# Clock.net
KiCad netlist of a schematic drawn in Altium Designer
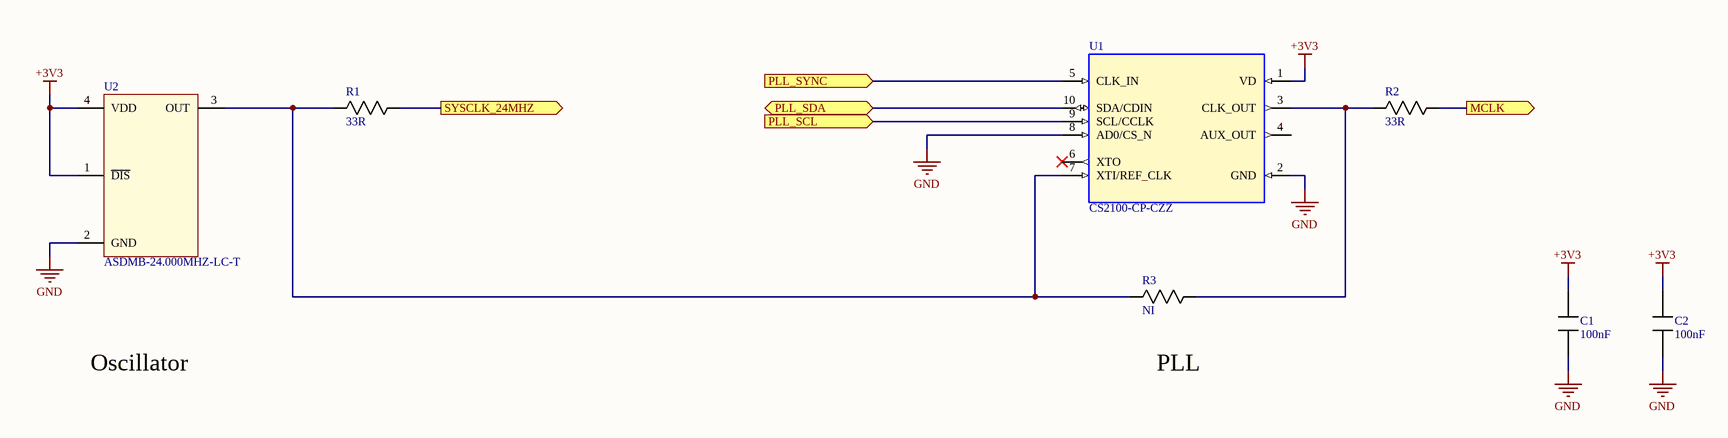
[diagram p0: Clock.SchDoc]

(export (version "E")
  (design (tool "Eeschema 10.0.6"))
  (components
    (comp (ref "C1")
      (value "100nF")
      (footprint "0603")
      (description "Capacitor")
      (fields (field (name "MFG") "Samsung"))
      (libsource (lib "ADAPTONE_CARTE_DE_SON") (part "Capacitor"))
    )
    (comp (ref "C2")
      (value "100nF")
      (footprint "0603")
      (description "Capacitor")
      (fields (field (name "MFG") "Samsung"))
      (libsource (lib "ADAPTONE_CARTE_DE_SON") (part "Capacitor"))
    )
    (comp (ref "R1")
      (value "33R")
      (footprint "0603")
      (description "Resistor")
      (fields (field (name "MFG") "Yageo"))
      (libsource (lib "ADAPTONE_CARTE_DE_SON") (part "Resistor"))
    )
    (comp (ref "R2")
      (value "33R")
      (footprint "0603")
      (description "Resistor")
      (fields (field (name "MFG") "Yageo"))
      (libsource (lib "ADAPTONE_CARTE_DE_SON") (part "Resistor"))
    )
    (comp (ref "R3")
      (value "Resistor")
      (footprint "0603")
      (fields (field (name "NI") "NI"))
      (libsource (lib "ADAPTONE_CARTE_DE_SON") (part "Resistor"))
    )
    (comp (ref "U1")
      (value "CS2100_CP")
      (footprint "MSOP10")
      (description "Fractional-N Clock Multiplier, Crystal Reference, MSOP10")
      (fields (field (name "MFG") "Cirrus Logic") (field (name "MFG_PN") "CS2100-CP-CZZ"))
      (libsource (lib "ADAPTONE_CARTE_DE_SON") (part "CS2100_CP"))
    )
    (comp (ref "U2")
      (value "OSC_ASDMB")
      (footprint "OSC_ADSMB")
      (description "Oscillator; 1V8 to 3V3")
      (fields (field (name "MFG") "Abracon") (field (name "MFG_PN") "ASDMB-24.000MHZ-LC-T"))
      (libsource (lib "ADAPTONE_CARTE_DE_SON") (part "OSC_ASDMB"))
    )
  )
  (nets
    (net (code "1") (name "+3V3") (class "Default")
      (node (ref "C1") (pin "1") (pintype "passive"))
      (node (ref "C2") (pin "1") (pintype "passive"))
      (node (ref "U1") (pin "1") (pinfunction "VD_1") (pintype "input"))
      (node (ref "U2") (pin "1") (pinfunction "~{DIS}_1") (pintype "passive"))
      (node (ref "U2") (pin "4") (pinfunction "VDD_4") (pintype "passive"))
    )
    (net (code "2") (name "/MCLK") (class "Default") (node (ref "R2") (pin "2") (pintype "passive")))
    (net (code "3") (name "/PLL_SCL") (class "Default")
      (node (ref "U1") (pin "9") (pinfunction "SCL/CCLK_9") (pintype "input"))
    )
    (net (code "4") (name "/PLL_SDA") (class "Default")
      (node (ref "U1") (pin "10") (pinfunction "SDA/CDIN_10") (pintype "bidirectional"))
    )
    (net (code "5") (name "/PLL_SYNC") (class "Default")
      (node (ref "U1") (pin "5") (pinfunction "CLK_IN_5") (pintype "input"))
    )
    (net (code "6") (name "/SYSCLK_24MHZ") (class "Default") (node (ref "R1") (pin "2") (pintype "passive")))
    (net (code "7") (name "GND") (class "Default")
      (node (ref "C1") (pin "2") (pintype "passive"))
      (node (ref "C2") (pin "2") (pintype "passive"))
      (node (ref "U1") (pin "2") (pinfunction "GND_2") (pintype "input"))
      (node (ref "U1") (pin "8") (pinfunction "AD0/CS_N_8") (pintype "input"))
      (node (ref "U2") (pin "2") (pinfunction "GND_2") (pintype "passive"))
    )
    (net (code "8") (name "Net-(U1-CLK_OUT)") (class "Default")
      (node (ref "R2") (pin "1") (pintype "passive"))
      (node (ref "R3") (pin "2") (pintype "passive"))
      (node (ref "U1") (pin "3") (pinfunction "CLK_OUT_3") (pintype "output"))
    )
    (net (code "9") (name "Net-(U1-XTI{slash}REF_CLK)") (class "Default")
      (node (ref "R1") (pin "1") (pintype "passive"))
      (node (ref "R3") (pin "1") (pintype "passive"))
      (node (ref "U1") (pin "7") (pinfunction "XTI/REF_CLK_7") (pintype "input"))
      (node (ref "U2") (pin "3") (pinfunction "OUT_3") (pintype "passive"))
    )
    (net (code "10") (name "unconnected-(U1-AUX_OUT-Pad4)") (class "Default")
      (node (ref "U1") (pin "4") (pinfunction "AUX_OUT_4") (pintype "output"))
    )
    (net (code "11") (name "unconnected-(U1-XTO-Pad6)") (class "Default")
      (node (ref "U1") (pin "6") (pinfunction "XTO_6") (pintype "output+no_connect"))
    )
  )
)
